# Sheet5.net
KiCad netlist of a schematic drawn in Altium Designer
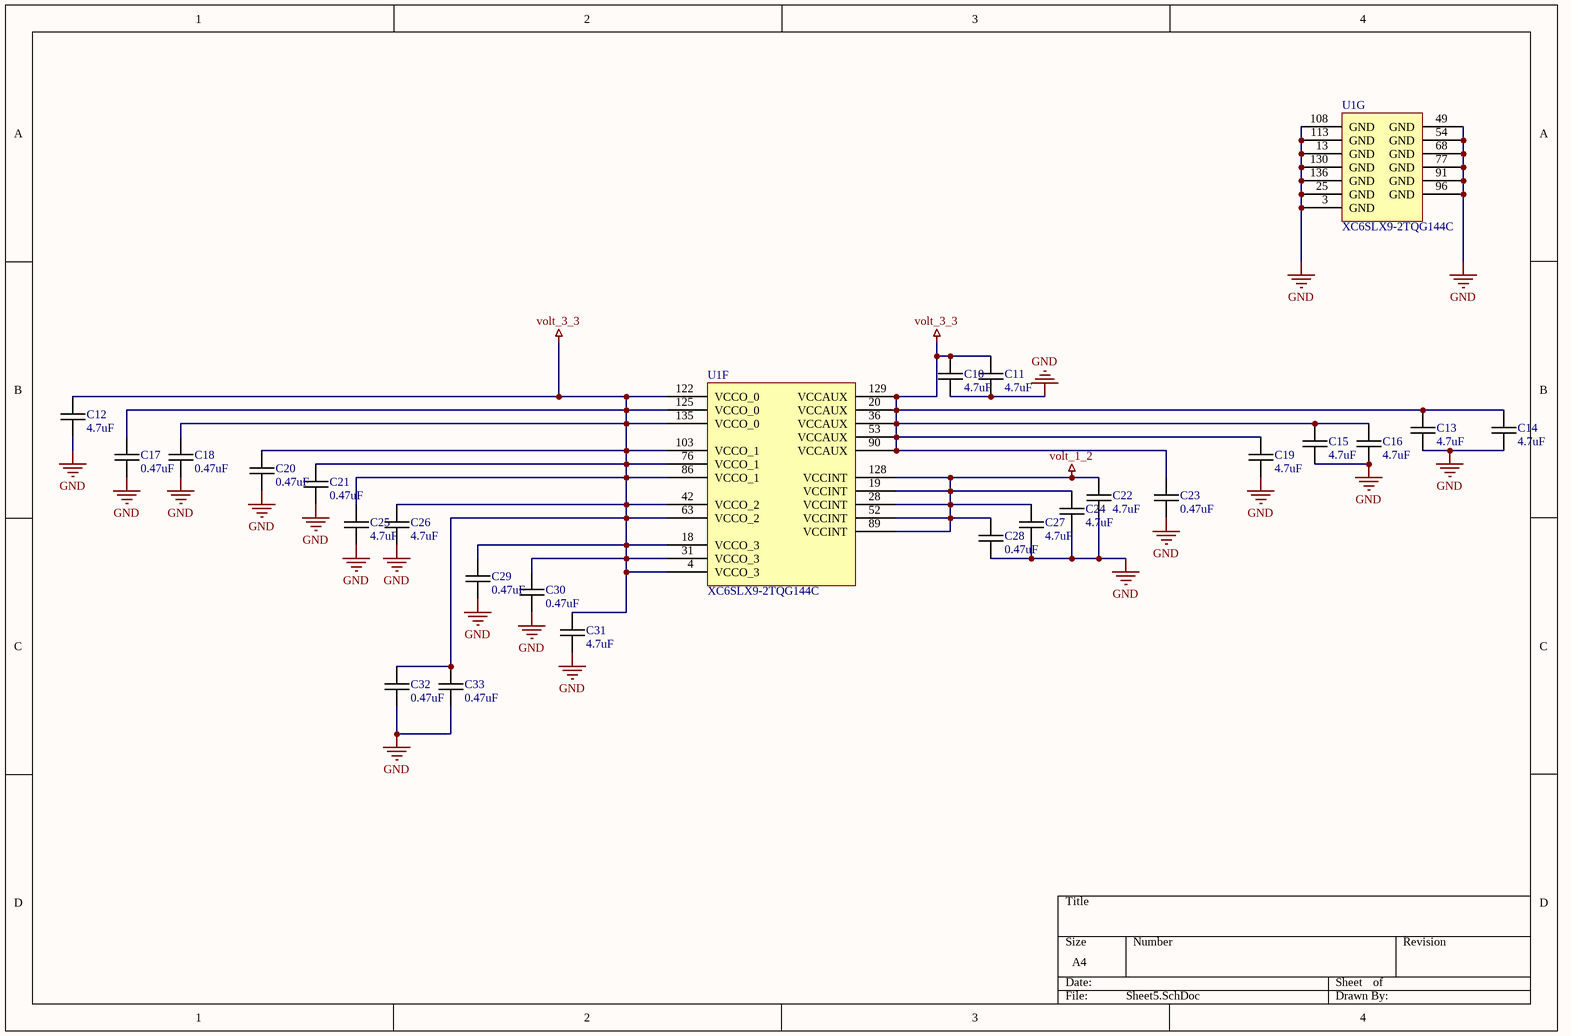
[diagram p0: Sheet5.SchDoc]

(export (version "E")
  (design (tool "Eeschema 10.0.6"))
  (components
    (comp (ref "C10")
      (value "4.7uF")
      (footprint "0805C-GENERIC")
      (description "CAPACITOR 0805 CERAMIC")
      (fields (field (name "TOLERANCE") "±10%") (field (name "MANUFACTURER") "TDK Corporation"))
      (libsource (lib "vh_altium_library") (part "0805C-4U7-25V-X5R-TDK"))
    )
    (comp (ref "C11")
      (value "4.7uF")
      (footprint "0805C-GENERIC")
      (description "CAPACITOR 0805 CERAMIC")
      (fields (field (name "TOLERANCE") "±10%") (field (name "MANUFACTURER") "TDK Corporation"))
      (libsource (lib "vh_altium_library") (part "0805C-4U7-25V-X5R-TDK"))
    )
    (comp (ref "C12")
      (value "4.7uF")
      (footprint "0805C-GENERIC")
      (description "CAPACITOR 0805 CERAMIC")
      (fields (field (name "TOLERANCE") "±10%") (field (name "MANUFACTURER") "TDK Corporation"))
      (libsource (lib "vh_altium_library") (part "0805C-4U7-25V-X5R-TDK"))
    )
    (comp (ref "C13")
      (value "4.7uF")
      (footprint "0805C-GENERIC")
      (description "CAPACITOR 0805 CERAMIC")
      (fields (field (name "TOLERANCE") "±10%") (field (name "MANUFACTURER") "TDK Corporation"))
      (libsource (lib "vh_altium_library") (part "0805C-4U7-25V-X5R-TDK"))
    )
    (comp (ref "C14")
      (value "4.7uF")
      (footprint "0805C-GENERIC")
      (description "CAPACITOR 0805 CERAMIC")
      (fields (field (name "TOLERANCE") "±10%") (field (name "MANUFACTURER") "TDK Corporation"))
      (libsource (lib "vh_altium_library") (part "0805C-4U7-25V-X5R-TDK"))
    )
    (comp (ref "C15")
      (value "4.7uF")
      (footprint "0805C-GENERIC")
      (description "CAPACITOR 0805 CERAMIC")
      (fields (field (name "TOLERANCE") "±10%") (field (name "MANUFACTURER") "TDK Corporation"))
      (libsource (lib "vh_altium_library") (part "0805C-4U7-25V-X5R-TDK"))
    )
    (comp (ref "C16")
      (value "4.7uF")
      (footprint "0805C-GENERIC")
      (description "CAPACITOR 0805 CERAMIC")
      (fields (field (name "TOLERANCE") "±10%") (field (name "MANUFACTURER") "TDK Corporation"))
      (libsource (lib "vh_altium_library") (part "0805C-4U7-25V-X5R-TDK"))
    )
    (comp (ref "C17")
      (value "0.47uF")
      (footprint "0805C-GENERIC")
      (description "CAPACITOR 0805 CERAMIC")
      (fields (field (name "TOLERANCE") "±10%") (field (name "MANUFACTURER") "TDK Corporation"))
      (libsource (lib "vh_altium_library") (part "0805C-4U7-25V-X5R-TDK"))
    )
    (comp (ref "C18")
      (value "0.47uF")
      (footprint "0805C-GENERIC")
      (description "CAPACITOR 0805 CERAMIC")
      (fields (field (name "TOLERANCE") "±10%") (field (name "MANUFACTURER") "TDK Corporation"))
      (libsource (lib "vh_altium_library") (part "0805C-4U7-25V-X5R-TDK"))
    )
    (comp (ref "C19")
      (value "4.7uF")
      (footprint "0805C-GENERIC")
      (description "CAPACITOR 0805 CERAMIC")
      (fields (field (name "TOLERANCE") "±10%") (field (name "MANUFACTURER") "TDK Corporation"))
      (libsource (lib "vh_altium_library") (part "0805C-4U7-25V-X5R-TDK"))
    )
    (comp (ref "C20")
      (value "0.47uF")
      (footprint "0805C-GENERIC")
      (description "CAPACITOR 0805 CERAMIC")
      (fields (field (name "TOLERANCE") "±10%") (field (name "MANUFACTURER") "TDK Corporation"))
      (libsource (lib "vh_altium_library") (part "0805C-4U7-25V-X5R-TDK"))
    )
    (comp (ref "C21")
      (value "0.47uF")
      (footprint "0805C-GENERIC")
      (description "CAPACITOR 0805 CERAMIC")
      (fields (field (name "TOLERANCE") "±10%") (field (name "MANUFACTURER") "TDK Corporation"))
      (libsource (lib "vh_altium_library") (part "0805C-4U7-25V-X5R-TDK"))
    )
    (comp (ref "C22")
      (value "4.7uF")
      (footprint "0805C-GENERIC")
      (description "CAPACITOR 0805 CERAMIC")
      (fields (field (name "TOLERANCE") "±10%") (field (name "MANUFACTURER") "TDK Corporation"))
      (libsource (lib "vh_altium_library") (part "0805C-4U7-25V-X5R-TDK"))
    )
    (comp (ref "C23")
      (value "0.47uF")
      (footprint "0805C-GENERIC")
      (description "CAPACITOR 0805 CERAMIC")
      (fields (field (name "TOLERANCE") "±10%") (field (name "MANUFACTURER") "TDK Corporation"))
      (libsource (lib "vh_altium_library") (part "0805C-4U7-25V-X5R-TDK"))
    )
    (comp (ref "C24")
      (value "4.7uF")
      (footprint "0805C-GENERIC")
      (description "CAPACITOR 0805 CERAMIC")
      (fields (field (name "TOLERANCE") "±10%") (field (name "MANUFACTURER") "TDK Corporation"))
      (libsource (lib "vh_altium_library") (part "0805C-4U7-25V-X5R-TDK"))
    )
    (comp (ref "C25")
      (value "4.7uF")
      (footprint "0805C-GENERIC")
      (description "CAPACITOR 0805 CERAMIC")
      (fields (field (name "TOLERANCE") "±10%") (field (name "MANUFACTURER") "TDK Corporation"))
      (libsource (lib "vh_altium_library") (part "0805C-4U7-25V-X5R-TDK"))
    )
    (comp (ref "C26")
      (value "4.7uF")
      (footprint "0805C-GENERIC")
      (description "CAPACITOR 0805 CERAMIC")
      (fields (field (name "TOLERANCE") "±10%") (field (name "MANUFACTURER") "TDK Corporation"))
      (libsource (lib "vh_altium_library") (part "0805C-4U7-25V-X5R-TDK"))
    )
    (comp (ref "C27")
      (value "4.7uF")
      (footprint "0805C-GENERIC")
      (description "CAPACITOR 0805 CERAMIC")
      (fields (field (name "TOLERANCE") "±10%") (field (name "MANUFACTURER") "TDK Corporation"))
      (libsource (lib "vh_altium_library") (part "0805C-4U7-25V-X5R-TDK"))
    )
    (comp (ref "C28")
      (value "0.47uF")
      (footprint "0805C-GENERIC")
      (description "CAPACITOR 0805 CERAMIC")
      (fields (field (name "TOLERANCE") "±10%") (field (name "MANUFACTURER") "TDK Corporation"))
      (libsource (lib "vh_altium_library") (part "0805C-4U7-25V-X5R-TDK"))
    )
    (comp (ref "C29")
      (value "0.47uF")
      (footprint "0805C-GENERIC")
      (description "CAPACITOR 0805 CERAMIC")
      (fields (field (name "TOLERANCE") "±10%") (field (name "MANUFACTURER") "TDK Corporation"))
      (libsource (lib "vh_altium_library") (part "0805C-4U7-25V-X5R-TDK"))
    )
    (comp (ref "C30")
      (value "0.47uF")
      (footprint "0805C-GENERIC")
      (description "CAPACITOR 0805 CERAMIC")
      (fields (field (name "TOLERANCE") "±10%") (field (name "MANUFACTURER") "TDK Corporation"))
      (libsource (lib "vh_altium_library") (part "0805C-4U7-25V-X5R-TDK"))
    )
    (comp (ref "C31")
      (value "4.7uF")
      (footprint "0805C-GENERIC")
      (description "CAPACITOR 0805 CERAMIC")
      (fields (field (name "TOLERANCE") "±10%") (field (name "MANUFACTURER") "TDK Corporation"))
      (libsource (lib "vh_altium_library") (part "0805C-4U7-25V-X5R-TDK"))
    )
    (comp (ref "C32")
      (value "0.47uF")
      (footprint "0805C-GENERIC")
      (description "CAPACITOR 0805 CERAMIC")
      (fields (field (name "TOLERANCE") "±10%") (field (name "MANUFACTURER") "TDK Corporation"))
      (libsource (lib "vh_altium_library") (part "0805C-4U7-25V-X5R-TDK"))
    )
    (comp (ref "C33")
      (value "0.47uF")
      (footprint "0805C-GENERIC")
      (description "CAPACITOR 0805 CERAMIC")
      (fields (field (name "TOLERANCE") "±10%") (field (name "MANUFACTURER") "TDK Corporation"))
      (libsource (lib "vh_altium_library") (part "0805C-4U7-25V-X5R-TDK"))
    )
    (comp (ref "U1")
      (value "XC6SLX9-2TQG144C")
      (footprint "TQG144_N")
      (libsource (lib "Xilinx Spartan-6") (part "XC6SLX9-2TQG144C"))
    )
  )
  (nets
    (net (code "1") (name "GND") (class "Default")
      (node (ref "C10") (pin "2") (pintype "passive"))
      (node (ref "C11") (pin "2") (pintype "passive"))
      (node (ref "C12") (pin "2") (pintype "passive"))
      (node (ref "C13") (pin "2") (pintype "passive"))
      (node (ref "C14") (pin "2") (pintype "passive"))
      (node (ref "C15") (pin "2") (pintype "passive"))
      (node (ref "C16") (pin "2") (pintype "passive"))
      (node (ref "C17") (pin "2") (pintype "passive"))
      (node (ref "C18") (pin "2") (pintype "passive"))
      (node (ref "C19") (pin "2") (pintype "passive"))
      (node (ref "C20") (pin "2") (pintype "passive"))
      (node (ref "C21") (pin "2") (pintype "passive"))
      (node (ref "C22") (pin "2") (pintype "passive"))
      (node (ref "C23") (pin "2") (pintype "passive"))
      (node (ref "C24") (pin "2") (pintype "passive"))
      (node (ref "C25") (pin "2") (pintype "passive"))
      (node (ref "C26") (pin "2") (pintype "passive"))
      (node (ref "C27") (pin "2") (pintype "passive"))
      (node (ref "C28") (pin "2") (pintype "passive"))
      (node (ref "C29") (pin "2") (pintype "passive"))
      (node (ref "C30") (pin "2") (pintype "passive"))
      (node (ref "C31") (pin "2") (pintype "passive"))
      (node (ref "C32") (pin "2") (pintype "passive"))
      (node (ref "C33") (pin "2") (pintype "passive"))
      (node (ref "U1") (pin "108") (pinfunction "GND_108") (pintype "power_in"))
      (node (ref "U1") (pin "113") (pinfunction "GND_113") (pintype "power_in"))
      (node (ref "U1") (pin "13") (pinfunction "GND_13") (pintype "power_in"))
      (node (ref "U1") (pin "130") (pinfunction "GND_130") (pintype "power_in"))
      (node (ref "U1") (pin "136") (pinfunction "GND_136") (pintype "power_in"))
      (node (ref "U1") (pin "25") (pinfunction "GND_25") (pintype "power_in"))
      (node (ref "U1") (pin "3") (pinfunction "GND_3") (pintype "power_in"))
      (node (ref "U1") (pin "49") (pinfunction "GND_49") (pintype "power_in"))
      (node (ref "U1") (pin "54") (pinfunction "GND_54") (pintype "power_in"))
      (node (ref "U1") (pin "68") (pinfunction "GND_68") (pintype "power_in"))
      (node (ref "U1") (pin "77") (pinfunction "GND_77") (pintype "power_in"))
      (node (ref "U1") (pin "91") (pinfunction "GND_91") (pintype "power_in"))
      (node (ref "U1") (pin "96") (pinfunction "GND_96") (pintype "power_in"))
    )
    (net (code "2") (name "volt_1_2") (class "Default")
      (node (ref "C22") (pin "1") (pintype "passive"))
      (node (ref "C24") (pin "1") (pintype "passive"))
      (node (ref "C27") (pin "1") (pintype "passive"))
      (node (ref "C28") (pin "1") (pintype "passive"))
      (node (ref "U1") (pin "128") (pinfunction "VCCINT_128") (pintype "power_in"))
      (node (ref "U1") (pin "19") (pinfunction "VCCINT_19") (pintype "power_in"))
      (node (ref "U1") (pin "28") (pinfunction "VCCINT_28") (pintype "power_in"))
      (node (ref "U1") (pin "52") (pinfunction "VCCINT_52") (pintype "power_in"))
      (node (ref "U1") (pin "89") (pinfunction "VCCINT_89") (pintype "power_in"))
    )
    (net (code "3") (name "volt_3_3") (class "Default")
      (node (ref "C10") (pin "1") (pintype "passive"))
      (node (ref "C11") (pin "1") (pintype "passive"))
      (node (ref "C12") (pin "1") (pintype "passive"))
      (node (ref "C13") (pin "1") (pintype "passive"))
      (node (ref "C14") (pin "1") (pintype "passive"))
      (node (ref "C15") (pin "1") (pintype "passive"))
      (node (ref "C16") (pin "1") (pintype "passive"))
      (node (ref "C17") (pin "1") (pintype "passive"))
      (node (ref "C18") (pin "1") (pintype "passive"))
      (node (ref "C19") (pin "1") (pintype "passive"))
      (node (ref "C20") (pin "1") (pintype "passive"))
      (node (ref "C21") (pin "1") (pintype "passive"))
      (node (ref "C23") (pin "1") (pintype "passive"))
      (node (ref "C25") (pin "1") (pintype "passive"))
      (node (ref "C26") (pin "1") (pintype "passive"))
      (node (ref "C29") (pin "1") (pintype "passive"))
      (node (ref "C30") (pin "1") (pintype "passive"))
      (node (ref "C31") (pin "1") (pintype "passive"))
      (node (ref "C32") (pin "1") (pintype "passive"))
      (node (ref "C33") (pin "1") (pintype "passive"))
      (node (ref "U1") (pin "103") (pinfunction "VCCO_1_103") (pintype "power_in"))
      (node (ref "U1") (pin "122") (pinfunction "VCCO_0_122") (pintype "power_in"))
      (node (ref "U1") (pin "125") (pinfunction "VCCO_0_125") (pintype "power_in"))
      (node (ref "U1") (pin "129") (pinfunction "VCCAUX_129") (pintype "power_in"))
      (node (ref "U1") (pin "135") (pinfunction "VCCO_0_135") (pintype "power_in"))
      (node (ref "U1") (pin "18") (pinfunction "VCCO_3_18") (pintype "power_in"))
      (node (ref "U1") (pin "20") (pinfunction "VCCAUX_20") (pintype "power_in"))
      (node (ref "U1") (pin "31") (pinfunction "VCCO_3_31") (pintype "power_in"))
      (node (ref "U1") (pin "36") (pinfunction "VCCAUX_36") (pintype "power_in"))
      (node (ref "U1") (pin "4") (pinfunction "VCCO_3_4") (pintype "power_in"))
      (node (ref "U1") (pin "42") (pinfunction "VCCO_2_42") (pintype "power_in"))
      (node (ref "U1") (pin "53") (pinfunction "VCCAUX_53") (pintype "power_in"))
      (node (ref "U1") (pin "63") (pinfunction "VCCO_2_63") (pintype "power_in"))
      (node (ref "U1") (pin "76") (pinfunction "VCCO_1_76") (pintype "power_in"))
      (node (ref "U1") (pin "86") (pinfunction "VCCO_1_86") (pintype "power_in"))
      (node (ref "U1") (pin "90") (pinfunction "VCCAUX_90") (pintype "power_in"))
    )
  )
)
